# Schematic.net
KiCad netlist of a schematic drawn in EAGLE
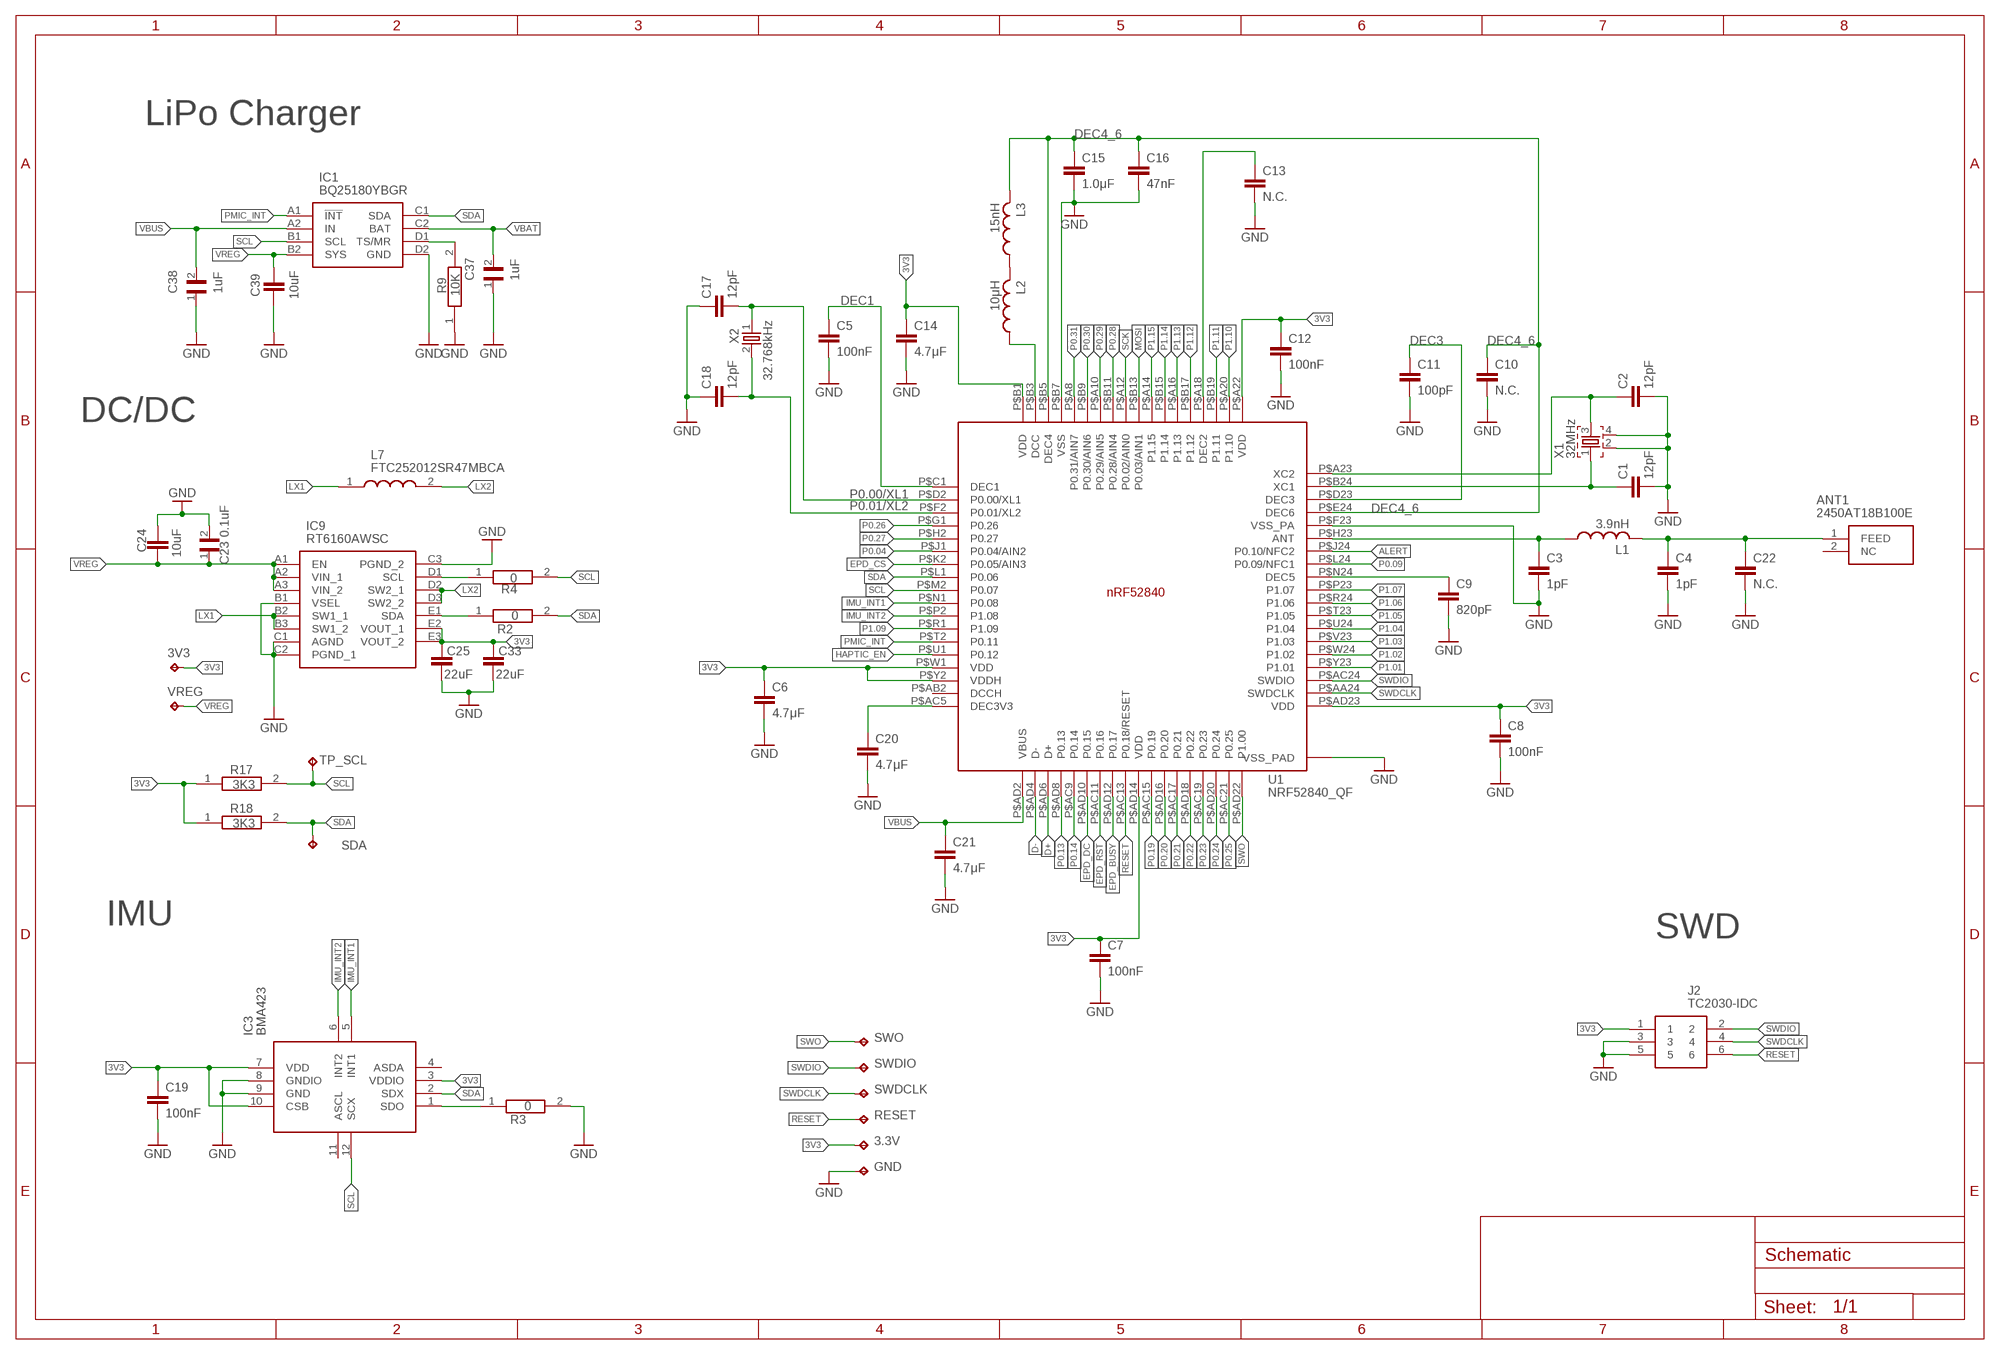
[diagram p0: schematic, sheet 1, part 1 of 2]
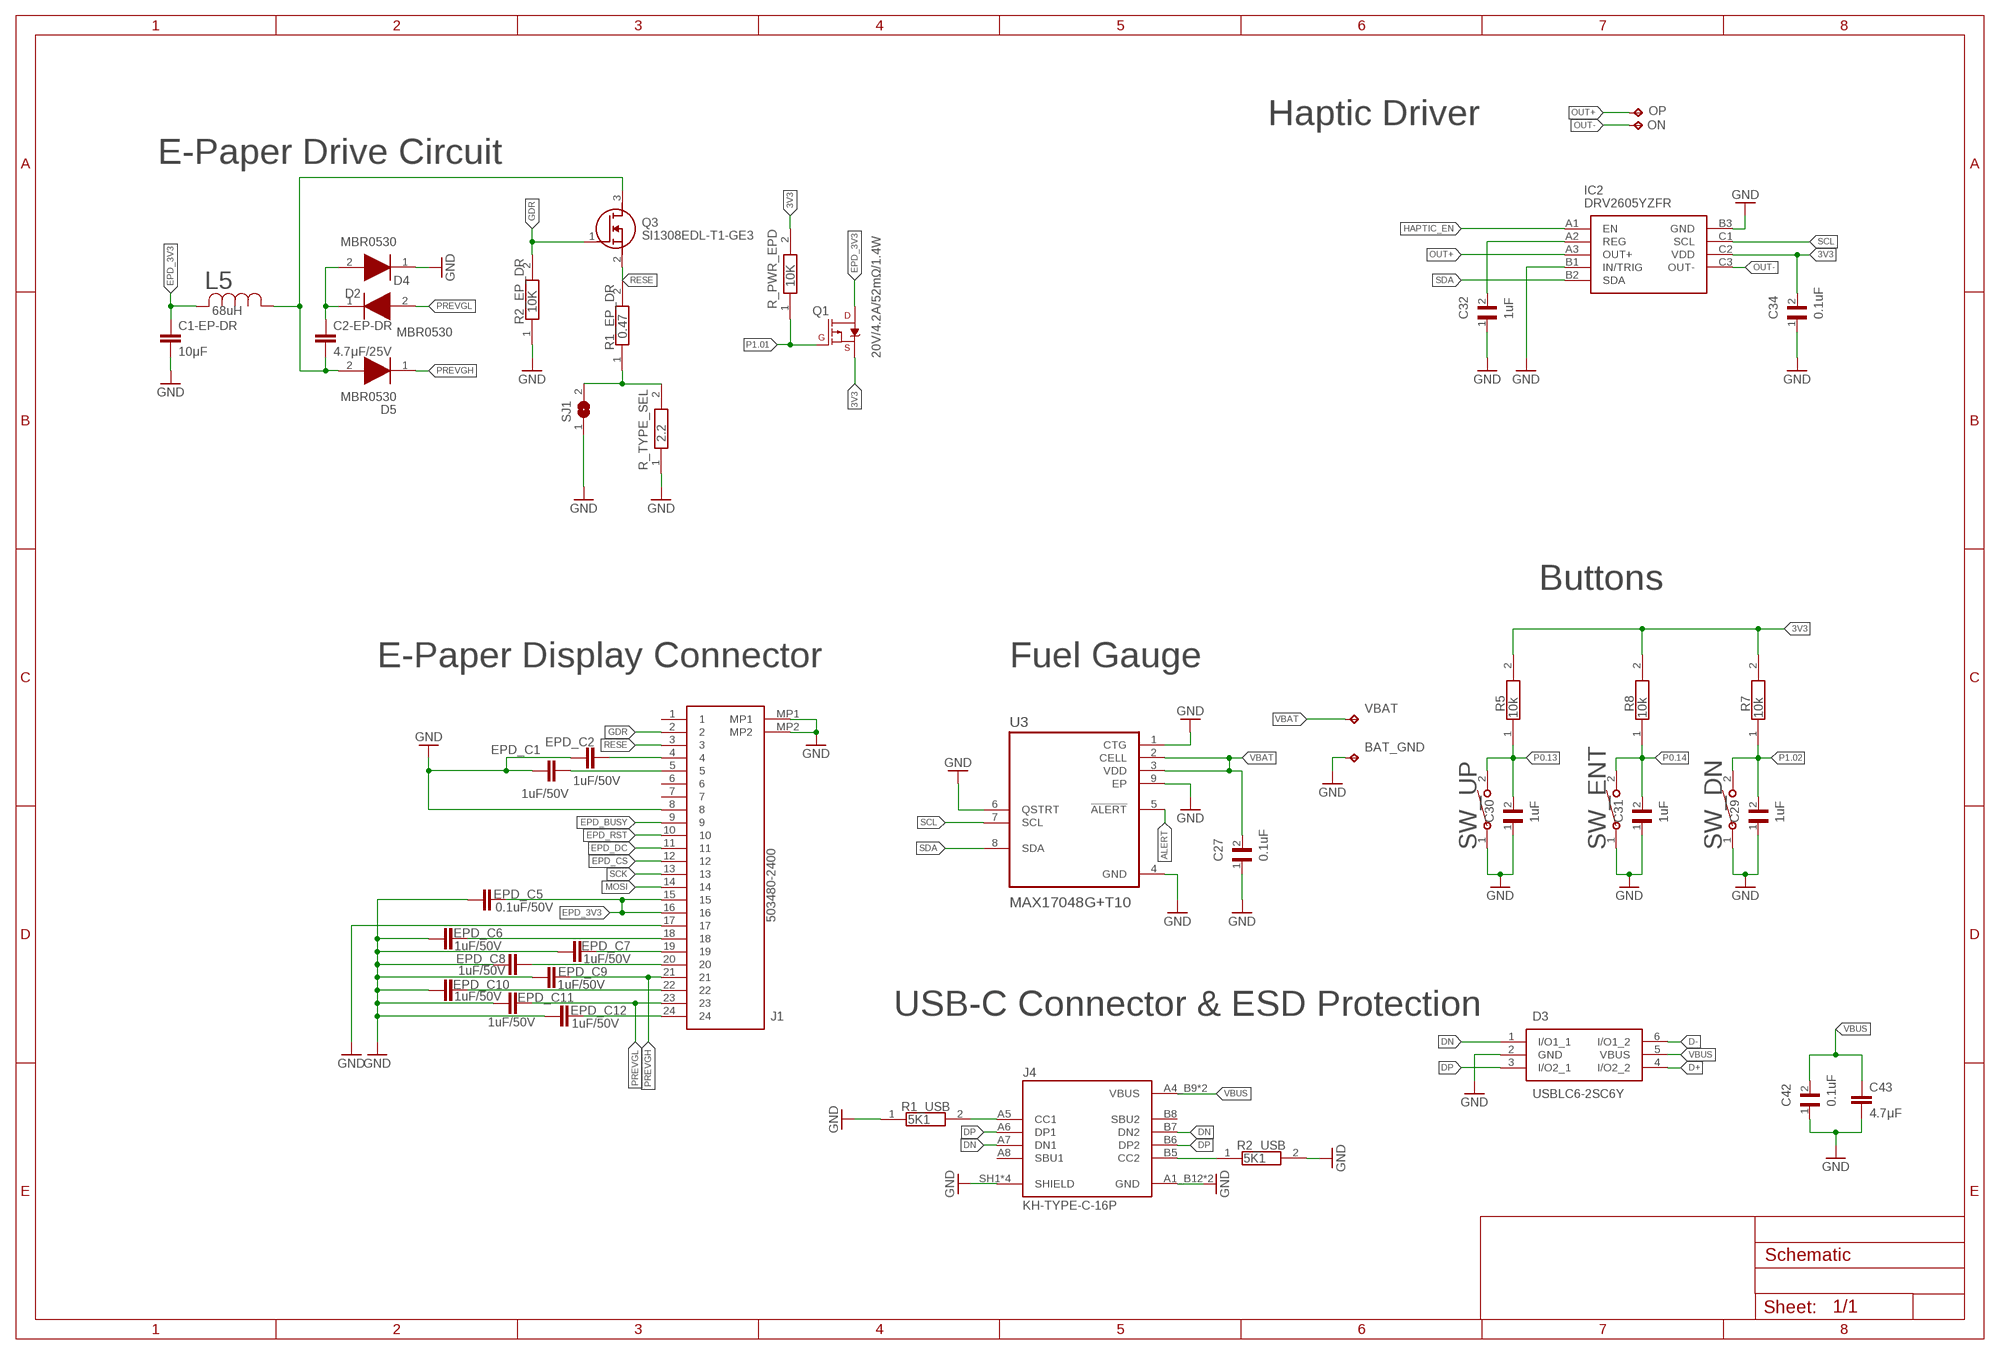
[diagram p1: schematic, sheet 1, part 2 of 2]

(export (version "E")
  (design (tool "Eeschema 10.0.6"))
  (components
    (comp (ref "3.3V")
      (value "HECTOR_WATCH_1_TPTP20R")
      (footprint "eagle-import:HECTOR_WATCH_1_TP20R")
      (libsource (lib "eagle-import") (part "HECTOR_WATCH_1_TPTP20R"))
    )
    (comp (ref "3V3")
      (value "HECTOR_WATCH_1_TPTP20R")
      (footprint "eagle-import:HECTOR_WATCH_1_TP20R")
      (libsource (lib "eagle-import") (part "HECTOR_WATCH_1_TPTP20R"))
    )
    (comp (ref "ANT1")
      (value "2450AT18B100E")
      (footprint "eagle-import:2450AT18B100E_ANTC3216X140N")
      (fields (field (name "MOUSER_PART_NUMBER") "609-2450AT18B100E"))
      (libsource (lib "eagle-import") (part "2450AT18B100E_2450AT18B100E"))
    )
    (comp (ref "BAT_GND")
      (value "HECTOR_WATCH_1_TPTP20R")
      (footprint "eagle-import:HECTOR_WATCH_1_TP20R")
      (libsource (lib "eagle-import") (part "HECTOR_WATCH_1_TPTP20R"))
    )
    (comp (ref "C1")
      (value "12pF")
      (footprint "eagle-import:GRM011R60J152KE01L_2_CAPC0201X13N")
      (libsource (lib "eagle-import") (part "NORDIC_NRF_3_CAPACITOR_0201_L"))
    )
    (comp (ref "C1-EP-DR")
      (value "10μF")
      (footprint "eagle-import:NORDIC_NRF_2_RESC0402_L")
      (libsource (lib "eagle-import") (part "NORDIC_NRF_3_CAPACITOR_0402_L"))
    )
    (comp (ref "C2")
      (value "12pF")
      (footprint "eagle-import:GRM011R60J152KE01L_2_CAPC0201X13N")
      (libsource (lib "eagle-import") (part "NORDIC_NRF_3_CAPACITOR_0201_L"))
    )
    (comp (ref "C2-EP-DR")
      (value "4.7μF/25V")
      (footprint "eagle-import:NORDIC_NRF_2_RESC0402_L")
      (libsource (lib "eagle-import") (part "NORDIC_NRF_3_CAPACITOR_0402_L"))
    )
    (comp (ref "C3")
      (value "1pF")
      (footprint "eagle-import:GRM011R60J152KE01L_2_CAPC0201X13N")
      (libsource (lib "eagle-import") (part "NORDIC_NRF_3_CAPACITOR_0201_L"))
    )
    (comp (ref "C4")
      (value "1pF")
      (footprint "eagle-import:GRM011R60J152KE01L_2_CAPC0201X13N")
      (libsource (lib "eagle-import") (part "NORDIC_NRF_3_CAPACITOR_0201_L"))
    )
    (comp (ref "C5")
      (value "100nF")
      (footprint "eagle-import:GRM011R60J152KE01L_2_CAPC0201X13N")
      (libsource (lib "eagle-import") (part "NORDIC_NRF_3_CAPACITOR_0201_L"))
    )
    (comp (ref "C6")
      (value "4.7μF")
      (footprint "eagle-import:NORDIC_NRF_2_RESC0402_L")
      (libsource (lib "eagle-import") (part "NORDIC_NRF_3_CAPACITOR_0402_L"))
    )
    (comp (ref "C7")
      (value "100nF")
      (footprint "eagle-import:GRM011R60J152KE01L_2_CAPC0201X13N")
      (libsource (lib "eagle-import") (part "NORDIC_NRF_3_CAPACITOR_0201_L"))
    )
    (comp (ref "C8")
      (value "100nF")
      (footprint "eagle-import:GRM011R60J152KE01L_2_CAPC0201X13N")
      (libsource (lib "eagle-import") (part "NORDIC_NRF_3_CAPACITOR_0201_L"))
    )
    (comp (ref "C9")
      (value "820pF")
      (footprint "eagle-import:GRM011R60J152KE01L_2_CAPC0201X13N")
      (libsource (lib "eagle-import") (part "NORDIC_NRF_3_CAPACITOR_0201_L"))
    )
    (comp (ref "C10")
      (value "N.C.")
      (footprint "eagle-import:GRM011R60J152KE01L_2_CAPC0201X13N")
      (libsource (lib "eagle-import") (part "NORDIC_NRF_3_CAPACITOR_0201_L"))
    )
    (comp (ref "C11")
      (value "100pF")
      (footprint "eagle-import:GRM011R60J152KE01L_2_CAPC0201X13N")
      (libsource (lib "eagle-import") (part "NORDIC_NRF_3_CAPACITOR_0201_L"))
    )
    (comp (ref "C12")
      (value "100nF")
      (footprint "eagle-import:GRM011R60J152KE01L_2_CAPC0201X13N")
      (libsource (lib "eagle-import") (part "NORDIC_NRF_3_CAPACITOR_0201_L"))
    )
    (comp (ref "C13")
      (value "N.C.")
      (footprint "eagle-import:GRM011R60J152KE01L_2_CAPC0201X13N")
      (libsource (lib "eagle-import") (part "NORDIC_NRF_3_CAPACITOR_0201_L"))
    )
    (comp (ref "C14")
      (value "4.7μF")
      (footprint "eagle-import:NORDIC_NRF_2_RESC0402_L")
      (libsource (lib "eagle-import") (part "NORDIC_NRF_3_CAPACITOR_0402_L"))
    )
    (comp (ref "C15")
      (value "1.0μF")
      (footprint "eagle-import:NORDIC_NRF_2_RESC0402_L")
      (libsource (lib "eagle-import") (part "NORDIC_NRF_3_CAPACITOR_0402_L"))
    )
    (comp (ref "C16")
      (value "47nF")
      (footprint "eagle-import:GRM011R60J152KE01L_2_CAPC0201X13N")
      (libsource (lib "eagle-import") (part "NORDIC_NRF_3_CAPACITOR_0201_L"))
    )
    (comp (ref "C17")
      (value "12pF")
      (footprint "eagle-import:GRM011R60J152KE01L_2_CAPC0201X13N")
      (libsource (lib "eagle-import") (part "NORDIC_NRF_3_CAPACITOR_0201_L"))
    )
    (comp (ref "C18")
      (value "12pF")
      (footprint "eagle-import:GRM011R60J152KE01L_2_CAPC0201X13N")
      (libsource (lib "eagle-import") (part "NORDIC_NRF_3_CAPACITOR_0201_L"))
    )
    (comp (ref "C19")
      (value "100nF")
      (footprint "eagle-import:GRM011R60J152KE01L_2_CAPC0201X13N")
      (libsource (lib "eagle-import") (part "NORDIC_NRF_3_CAPACITOR_0201_L"))
    )
    (comp (ref "C20")
      (value "4.7μF")
      (footprint "eagle-import:NORDIC_NRF_2_RESC0402_L")
      (libsource (lib "eagle-import") (part "NORDIC_NRF_3_CAPACITOR_0402_L"))
    )
    (comp (ref "C21")
      (value "4.7μF")
      (footprint "eagle-import:NORDIC_NRF_2_RESC0402_L")
      (libsource (lib "eagle-import") (part "NORDIC_NRF_3_CAPACITOR_0402_L"))
    )
    (comp (ref "C22")
      (value "N.C.")
      (footprint "eagle-import:GRM011R60J152KE01L_2_CAPC0201X13N")
      (libsource (lib "eagle-import") (part "NORDIC_NRF_3_CAPACITOR_0201_L"))
    )
    (comp (ref "C23")
      (value "0.1uF")
      (footprint "eagle-import:GRM011R60J152KE01L_2_CAPC0201X13N")
      (fields (field (name "MF") "Murata") (field (name "MP") "GRM011R60J152KE01L"))
      (libsource (lib "eagle-import") (part "GRM011R60J152KE01L_2_GRM011R60J152KE01L"))
    )
    (comp (ref "C24")
      (value "10uF")
      (footprint "eagle-import:PERFECT_0402_0402")
      (libsource (lib "eagle-import") (part "PERFECT_0402_CAP_0402"))
    )
    (comp (ref "C25")
      (value "22uF")
      (footprint "eagle-import:PERFECT_0402_0402")
      (libsource (lib "eagle-import") (part "PERFECT_0402_CAP_0402"))
    )
    (comp (ref "C27")
      (value "0.1uF")
      (footprint "eagle-import:GRM011R60J152KE01L_2_CAPC0201X13N")
      (fields (field (name "MF") "Murata") (field (name "MP") "GRM011R60J152KE01L"))
      (libsource (lib "eagle-import") (part "GRM011R60J152KE01L_2_GRM011R60J152KE01L"))
    )
    (comp (ref "C29")
      (value "1uF")
      (footprint "eagle-import:GRM011R60J152KE01L_2_CAPC0201X13N")
      (fields (field (name "MF") "Murata") (field (name "MP") "GRM011R60J152KE01L"))
      (libsource (lib "eagle-import") (part "GRM011R60J152KE01L_2_GRM011R60J152KE01L"))
    )
    (comp (ref "C30")
      (value "1uF")
      (footprint "eagle-import:GRM011R60J152KE01L_2_CAPC0201X13N")
      (fields (field (name "MF") "Murata") (field (name "MP") "GRM011R60J152KE01L"))
      (libsource (lib "eagle-import") (part "GRM011R60J152KE01L_2_GRM011R60J152KE01L"))
    )
    (comp (ref "C31")
      (value "1uF")
      (footprint "eagle-import:GRM011R60J152KE01L_2_CAPC0201X13N")
      (fields (field (name "MF") "Murata") (field (name "MP") "GRM011R60J152KE01L"))
      (libsource (lib "eagle-import") (part "GRM011R60J152KE01L_2_GRM011R60J152KE01L"))
    )
    (comp (ref "C32")
      (value "1uF")
      (footprint "eagle-import:GRM011R60J152KE01L_2_CAPC0201X13N")
      (fields (field (name "MF") "Murata") (field (name "MP") "GRM011R60J152KE01L"))
      (libsource (lib "eagle-import") (part "GRM011R60J152KE01L_2_GRM011R60J152KE01L"))
    )
    (comp (ref "C33")
      (value "22uF")
      (footprint "eagle-import:PERFECT_0402_0402")
      (libsource (lib "eagle-import") (part "PERFECT_0402_CAP_0402"))
    )
    (comp (ref "C34")
      (value "0.1uF")
      (footprint "eagle-import:GRM011R60J152KE01L_2_CAPC0201X13N")
      (fields (field (name "MF") "Murata") (field (name "MP") "GRM011R60J152KE01L"))
      (libsource (lib "eagle-import") (part "GRM011R60J152KE01L_2_GRM011R60J152KE01L"))
    )
    (comp (ref "C37")
      (value "1uF")
      (footprint "eagle-import:GRM011R60J152KE01L_2_CAPC0201X13N")
      (fields (field (name "MF") "Murata") (field (name "MP") "GRM011R60J152KE01L"))
      (libsource (lib "eagle-import") (part "GRM011R60J152KE01L_2_GRM011R60J152KE01L"))
    )
    (comp (ref "C38")
      (value "1uF")
      (footprint "eagle-import:GRM011R60J152KE01L_2_CAPC0201X13N")
      (fields (field (name "MF") "Murata") (field (name "MP") "GRM011R60J152KE01L"))
      (libsource (lib "eagle-import") (part "GRM011R60J152KE01L_2_GRM011R60J152KE01L"))
    )
    (comp (ref "C39")
      (value "10uF")
      (footprint "eagle-import:NORDIC_NRF_2_RESC0402_L")
      (libsource (lib "eagle-import") (part "NORDIC_NRF_3_CAPACITOR_0402_L"))
    )
    (comp (ref "C42")
      (value "0.1uF")
      (footprint "eagle-import:GRM011R60J152KE01L_2_CAPC0201X13N")
      (fields (field (name "MF") "Murata") (field (name "MP") "GRM011R60J152KE01L"))
      (libsource (lib "eagle-import") (part "GRM011R60J152KE01L_2_GRM011R60J152KE01L"))
    )
    (comp (ref "C43")
      (value "4.7μF")
      (footprint "eagle-import:NORDIC_NRF_2_RESC0402_L")
      (libsource (lib "eagle-import") (part "NORDIC_NRF_3_CAPACITOR_0402_L"))
    )
    (comp (ref "D2")
      (value "MBR0530")
      (footprint "eagle-import:ESP32_C6_LIBRARY_5_SOD3716X135N")
      (fields (field (name "MF") "ON Semiconductor"))
      (libsource (lib "eagle-import") (part "ESP32_C6_LIBRARY_5_MBR0530"))
    )
    (comp (ref "D3")
      (value "USBLC6-2SC6Y")
      (footprint "eagle-import:ESP32_C6_LIBRARY_3_SOT95P280X145-6N")
      (fields (field (name "MF") "STMicroelectronics"))
      (libsource (lib "eagle-import") (part "ESP32_C6_LIBRARY_3_USBLC6-2SC6Y"))
    )
    (comp (ref "D4")
      (value "MBR0530")
      (footprint "eagle-import:ESP32_C6_LIBRARY_5_SOD3716X135N")
      (fields (field (name "MF") "ON Semiconductor"))
      (libsource (lib "eagle-import") (part "ESP32_C6_LIBRARY_5_MBR0530"))
    )
    (comp (ref "D5")
      (value "MBR0530")
      (footprint "eagle-import:ESP32_C6_LIBRARY_5_SOD3716X135N")
      (fields (field (name "MF") "ON Semiconductor"))
      (libsource (lib "eagle-import") (part "ESP32_C6_LIBRARY_5_MBR0530"))
    )
    (comp (ref "EPD_C1")
      (value "1uF/50V")
      (footprint "eagle-import:GRM011R60J152KE01L_2_CAPC0201X13N")
      (libsource (lib "eagle-import") (part "NORDIC_NRF_3_CAPACITOR_0201_L"))
    )
    (comp (ref "EPD_C2")
      (value "1uF/50V")
      (footprint "eagle-import:GRM011R60J152KE01L_2_CAPC0201X13N")
      (libsource (lib "eagle-import") (part "NORDIC_NRF_3_CAPACITOR_0201_L"))
    )
    (comp (ref "EPD_C5")
      (value "0.1uF/50V")
      (footprint "eagle-import:GRM011R60J152KE01L_2_CAPC0201X13N")
      (libsource (lib "eagle-import") (part "NORDIC_NRF_3_CAPACITOR_0201_L"))
    )
    (comp (ref "EPD_C6")
      (value "1uF/50V")
      (footprint "eagle-import:GRM011R60J152KE01L_2_CAPC0201X13N")
      (libsource (lib "eagle-import") (part "NORDIC_NRF_3_CAPACITOR_0201_L"))
    )
    (comp (ref "EPD_C7")
      (value "1uF/50V")
      (footprint "eagle-import:GRM011R60J152KE01L_2_CAPC0201X13N")
      (libsource (lib "eagle-import") (part "NORDIC_NRF_3_CAPACITOR_0201_L"))
    )
    (comp (ref "EPD_C8")
      (value "1uF/50V")
      (footprint "eagle-import:GRM011R60J152KE01L_2_CAPC0201X13N")
      (libsource (lib "eagle-import") (part "NORDIC_NRF_3_CAPACITOR_0201_L"))
    )
    (comp (ref "EPD_C9")
      (value "1uF/50V")
      (footprint "eagle-import:GRM011R60J152KE01L_2_CAPC0201X13N")
      (libsource (lib "eagle-import") (part "NORDIC_NRF_3_CAPACITOR_0201_L"))
    )
    (comp (ref "EPD_C10")
      (value "1uF/50V")
      (footprint "eagle-import:GRM011R60J152KE01L_2_CAPC0201X13N")
      (libsource (lib "eagle-import") (part "NORDIC_NRF_3_CAPACITOR_0201_L"))
    )
    (comp (ref "EPD_C11")
      (value "1uF/50V")
      (footprint "eagle-import:GRM011R60J152KE01L_2_CAPC0201X13N")
      (libsource (lib "eagle-import") (part "NORDIC_NRF_3_CAPACITOR_0201_L"))
    )
    (comp (ref "EPD_C12")
      (value "1uF/50V")
      (footprint "eagle-import:GRM011R60J152KE01L_2_CAPC0201X13N")
      (libsource (lib "eagle-import") (part "NORDIC_NRF_3_CAPACITOR_0201_L"))
    )
    (comp (ref "GND")
      (value "HECTOR_WATCH_1_TPTP20R")
      (footprint "eagle-import:HECTOR_WATCH_1_TP20R")
      (libsource (lib "eagle-import") (part "HECTOR_WATCH_1_TPTP20R"))
    )
    (comp (ref "IC1")
      (value "BQ25180YBGR")
      (footprint "eagle-import:BQ25180YBGR_BGA8C40P2X4_100X155X50")
      (fields (field (name "MOUSER_PART_NUMBER") "595-BQ25180YBGR"))
      (libsource (lib "eagle-import") (part "BQ25180YBGR_BQ25180YBGR"))
    )
    (comp (ref "IC2")
      (value "DRV2605YZFR")
      (footprint "eagle-import:DRV2605YZFR_BGA9C50P3X3_144X144X62")
      (libsource (lib "eagle-import") (part "DRV2605YZFR_DRV2605YZFR"))
    )
    (comp (ref "IC3")
      (value "BMA423")
      (footprint "eagle-import:BMA423_BMA423")
      (fields (field (name "MOUSER_PART_NUMBER") "262-BMA423"))
      (libsource (lib "eagle-import") (part "BMA423_BMA423"))
    )
    (comp (ref "IC9")
      (value "RT6160AWSC")
      (footprint "eagle-import:RT6160AWSC_BGA15C40P3X5_140X230X60")
      (fields (field (name "MOUSER_PART_NUMBER") "835-RT6160AWSC"))
      (libsource (lib "eagle-import") (part "RT6160AWSC_RT6160AWSC"))
    )
    (comp (ref "J1")
      (value "503480-2400")
      (footprint "eagle-import:503480-2400_5034802400")
      (fields (field (name "MOUSER_PART_NUMBER") "538-503480-2400"))
      (libsource (lib "eagle-import") (part "503480-2400_503480-2400"))
    )
    (comp (ref "J2")
      (value "TC2030-IDC")
      (footprint "eagle-import:TC2030-IDC_TC2030IDC")
      (libsource (lib "eagle-import") (part "TC2030-IDC_TC2030-IDC"))
    )
    (comp (ref "J4")
      (value "KH-TYPE-C-16P")
      (footprint "eagle-import:KH-TYPE-C-16P_KINGHELM_KH-TYPE-C-16P")
      (fields (field (name "MF") "kinghelm"))
      (libsource (lib "eagle-import") (part "KH-TYPE-C-16P_KH-TYPE-C-16P"))
    )
    (comp (ref "L1")
      (value "3.9nH")
      (footprint "eagle-import:NORDIC_NRF_2_RESC0201_L")
      (libsource (lib "eagle-import") (part "NORDIC_NRF_2_INDUCTOR_0201_L"))
    )
    (comp (ref "L2")
      (value "10μH")
      (footprint "eagle-import:NORDIC_NRF_2_RESC0201_L")
      (libsource (lib "eagle-import") (part "NORDIC_NRF_2_INDUCTOR_0201_L"))
    )
    (comp (ref "L3")
      (value "15nH")
      (footprint "eagle-import:NORDIC_NRF_2_RESC0201_L")
      (libsource (lib "eagle-import") (part "NORDIC_NRF_2_INDUCTOR_0201_L"))
    )
    (comp (ref "L5")
      (value "68uH")
      (footprint "eagle-import:ESP32_C6_LIBRARY_2_IND_4828-WE-TPC_WRE")
      (fields
        (field (name "MANUFACTURER_PART_NUMBER") "744043680")
        (field (name "COPYRIGHT") "Copyright (C) 2024 Ultra Librarian. All rights reserved.")
      )
      (libsource (lib "eagle-import") (part "ESP32_C6_LIBRARY_2_744043680IND_4828-WE-TPC_WRE"))
    )
    (comp (ref "L7")
      (value "FTC252012SR47MBCA")
      (footprint "eagle-import:MLP2016SR47MT0S1_INDC2016X100N")
      (libsource (lib "eagle-import") (part "MLP2016SR47MT0S1_FTC252012SR47MBCA"))
    )
    (comp (ref "ON")
      (value "HECTOR_WATCH_1_TPTP20R")
      (footprint "eagle-import:HECTOR_WATCH_1_TP20R")
      (libsource (lib "eagle-import") (part "HECTOR_WATCH_1_TPTP20R"))
    )
    (comp (ref "OP")
      (value "HECTOR_WATCH_1_TPTP20R")
      (footprint "eagle-import:HECTOR_WATCH_1_TP20R")
      (libsource (lib "eagle-import") (part "HECTOR_WATCH_1_TPTP20R"))
    )
    (comp (ref "Q1")
      (value "20V/4.2A/52mΩ/1.4W")
      (footprint "eagle-import:ESP32_C6_LIBRARY_4_ESP32_C6_LIBRARY_4_ESP32_C6_LIBRARY_4_ESP32_C6_LIBRARY_4_ESP32_WROVER_SPARKFUN-DISCRETESEMI_SOT23-3")
      (libsource (lib "eagle-import") (part "ESP32_C6_LIBRARY_4_ESP32_WROVER_SPARKFUN-DISCRETESEMI_MOSFET_PCH-DMG2305UX-7"))
    )
    (comp (ref "Q3")
      (value "SI1308EDL-T1-GE3")
      (footprint "eagle-import:ESP32_C6_LIBRARY_6_SOT65P210X110-3N")
      (fields (field (name "MF") "Vishay Siliconix"))
      (libsource (lib "eagle-import") (part "ESP32_C6_LIBRARY_6_SI1308EDL-T1-GE3"))
    )
    (comp (ref "R1_EP_DR")
      (value "0.47")
      (footprint "eagle-import:ERA-1AEB3401C_0201")
      (libsource (lib "eagle-import") (part "CPF0201D7K68C1_CPF0201D7K68C1"))
    )
    (comp (ref "R1_USB")
      (value "5K1")
      (footprint "eagle-import:ERA-1AEB3401C_0201")
      (libsource (lib "eagle-import") (part "CPF0201D7K68C1_CPF0201D7K68C1"))
    )
    (comp (ref "R2")
      (value "0")
      (footprint "eagle-import:ERA-1AEB3401C_0201")
      (fields (field (name "RESISTANCE") "0"))
      (libsource (lib "eagle-import") (part "CPF0201D7K68C1_CPF0201D7K68C1"))
    )
    (comp (ref "R2_EP_DR")
      (value "10K")
      (footprint "eagle-import:ERA-1AEB3401C_0201")
      (libsource (lib "eagle-import") (part "CPF0201D7K68C1_CPF0201D7K68C1"))
    )
    (comp (ref "R2_USB")
      (value "5K1")
      (footprint "eagle-import:ERA-1AEB3401C_0201")
      (libsource (lib "eagle-import") (part "CPF0201D7K68C1_CPF0201D7K68C1"))
    )
    (comp (ref "R3")
      (value "0")
      (footprint "eagle-import:ERA-1AEB3401C_0201")
      (fields (field (name "RESISTANCE") "0"))
      (libsource (lib "eagle-import") (part "CPF0201D7K68C1_CPF0201D7K68C1"))
    )
    (comp (ref "R4")
      (value "0")
      (footprint "eagle-import:ERA-1AEB3401C_0201")
      (fields (field (name "RESISTANCE") "0"))
      (libsource (lib "eagle-import") (part "CPF0201D7K68C1_CPF0201D7K68C1"))
    )
    (comp (ref "R5")
      (value "10k")
      (footprint "eagle-import:ERA-1AEB3401C_0201")
      (libsource (lib "eagle-import") (part "CPF0201D7K68C1_CPF0201D7K68C1"))
    )
    (comp (ref "R7")
      (value "10k")
      (footprint "eagle-import:ERA-1AEB3401C_0201")
      (libsource (lib "eagle-import") (part "CPF0201D7K68C1_CPF0201D7K68C1"))
    )
    (comp (ref "R8")
      (value "10k")
      (footprint "eagle-import:ERA-1AEB3401C_0201")
      (libsource (lib "eagle-import") (part "CPF0201D7K68C1_CPF0201D7K68C1"))
    )
    (comp (ref "R9")
      (value "10K")
      (footprint "eagle-import:ERA-1AEB3401C_0201")
      (fields (field (name "RESISTANCE") "10K"))
      (libsource (lib "eagle-import") (part "CPF0201D7K68C1_CPF0201D7K68C1"))
    )
    (comp (ref "R17")
      (value "3K3")
      (footprint "eagle-import:ERA-1AEB3401C_0201")
      (fields (field (name "RESISTANCE") "3K3"))
      (libsource (lib "eagle-import") (part "CPF0201D7K68C1_CPF0201D7K68C1"))
    )
    (comp (ref "R18")
      (value "3K3")
      (footprint "eagle-import:ERA-1AEB3401C_0201")
      (fields (field (name "RESISTANCE") "3K3"))
      (libsource (lib "eagle-import") (part "CPF0201D7K68C1_CPF0201D7K68C1"))
    )
    (comp (ref "RESET")
      (value "HECTOR_WATCH_1_TPTP20R")
      (footprint "eagle-import:HECTOR_WATCH_1_TP20R")
      (libsource (lib "eagle-import") (part "HECTOR_WATCH_1_TPTP20R"))
    )
    (comp (ref "R_PWR_EPD")
      (value "10K")
      (footprint "eagle-import:ERA-1AEB3401C_0201")
      (libsource (lib "eagle-import") (part "CPF0201D7K68C1_CPF0201D7K68C1"))
    )
    (comp (ref "R_TYPE_SEL")
      (value "2.2")
      (footprint "eagle-import:ERA-1AEB3401C_0201")
      (libsource (lib "eagle-import") (part "CPF0201D7K68C1_CPF0201D7K68C1"))
    )
    (comp (ref "SDA")
      (value "HECTOR_WATCH_1_TPTP20R")
      (footprint "eagle-import:HECTOR_WATCH_1_TP20R")
      (libsource (lib "eagle-import") (part "HECTOR_WATCH_1_TPTP20R"))
    )
    (comp (ref "SJ1")
      (value "ESP32_C6_LIBRARY_7_JUMPER_SJ")
      (footprint "eagle-import:ESP32_C6_LIBRARY_7_JUMPER_SJ")
      (libsource (lib "eagle-import") (part "ESP32_C6_LIBRARY_7_JUMPER_SJ"))
    )
    (comp (ref "SWDCLK")
      (value "HECTOR_WATCH_1_TPTP20R")
      (footprint "eagle-import:HECTOR_WATCH_1_TP20R")
      (libsource (lib "eagle-import") (part "HECTOR_WATCH_1_TPTP20R"))
    )
    (comp (ref "SWDIO")
      (value "HECTOR_WATCH_1_TPTP20R")
      (footprint "eagle-import:HECTOR_WATCH_1_TP20R")
      (libsource (lib "eagle-import") (part "HECTOR_WATCH_1_TPTP20R"))
    )
    (comp (ref "SWO")
      (value "HECTOR_WATCH_1_TPTP20R")
      (footprint "eagle-import:HECTOR_WATCH_1_TP20R")
      (libsource (lib "eagle-import") (part "HECTOR_WATCH_1_TPTP20R"))
    )
    (comp (ref "SW_DN")
      (value "2025-10-22_07-23-44_LIBRARY_EVP-AKE31ASW_EVP-AKE31A_PAN")
      (footprint "eagle-import:2025-10-22_07-23-44_LIBRARY_SW_EVP-AKE31A_PAN")
      (fields
        (field (name "MANUFACTURER_PART_NUMBER") "EVP-AKE31A")
        (field (name "COPYRIGHT") "Copyright (C) 2025 Ultra Librarian. All rights reserved.")
      )
      (libsource (lib "eagle-import") (part "2025-10-22_07-23-44_LIBRARY_EVP-AKE31ASW_EVP-AKE31A_PAN"))
    )
    (comp (ref "SW_ENT")
      (value "2025-10-22_07-23-44_LIBRARY_EVP-AKE31ASW_EVP-AKE31A_PAN")
      (footprint "eagle-import:2025-10-22_07-23-44_LIBRARY_SW_EVP-AKE31A_PAN")
      (fields
        (field (name "MANUFACTURER_PART_NUMBER") "EVP-AKE31A")
        (field (name "COPYRIGHT") "Copyright (C) 2025 Ultra Librarian. All rights reserved.")
      )
      (libsource (lib "eagle-import") (part "2025-10-22_07-23-44_LIBRARY_EVP-AKE31ASW_EVP-AKE31A_PAN"))
    )
    (comp (ref "SW_UP")
      (value "2025-10-22_07-23-44_LIBRARY_EVP-AKE31ASW_EVP-AKE31A_PAN")
      (footprint "eagle-import:2025-10-22_07-23-44_LIBRARY_SW_EVP-AKE31A_PAN")
      (fields
        (field (name "MANUFACTURER_PART_NUMBER") "EVP-AKE31A")
        (field (name "COPYRIGHT") "Copyright (C) 2025 Ultra Librarian. All rights reserved.")
      )
      (libsource (lib "eagle-import") (part "2025-10-22_07-23-44_LIBRARY_EVP-AKE31ASW_EVP-AKE31A_PAN"))
    )
    (comp (ref "TP_SCL")
      (value "HECTOR_WATCH_1_TPTP20R")
      (footprint "eagle-import:HECTOR_WATCH_1_TP20R")
      (libsource (lib "eagle-import") (part "HECTOR_WATCH_1_TPTP20R"))
    )
    (comp (ref "U1")
      (value "NRF52840_QF")
      (footprint "eagle-import:NORDIC_NRF_4_AQFN50P700X700X85_HS-74N")
      (libsource (lib "eagle-import") (part "NORDIC_NRF_4_NRF52840_QF"))
    )
    (comp (ref "U3")
      (value "MAX17048G+T10")
      (footprint "eagle-import:ESP32_C6_LIBRARY_SON50P200X200X80-9N")
      (fields (field (name "MF") "Analog Devices"))
      (libsource (lib "eagle-import") (part "ESP32_C6_LIBRARY_MAX17048G+T10"))
    )
    (comp (ref "VBAT")
      (value "HECTOR_WATCH_1_TPTP20R")
      (footprint "eagle-import:HECTOR_WATCH_1_TP20R")
      (libsource (lib "eagle-import") (part "HECTOR_WATCH_1_TPTP20R"))
    )
    (comp (ref "VREG")
      (value "HECTOR_WATCH_1_TPTP20R")
      (footprint "eagle-import:HECTOR_WATCH_1_TP20R")
      (libsource (lib "eagle-import") (part "HECTOR_WATCH_1_TPTP20R"))
    )
    (comp (ref "X1")
      (value "32MHz")
      (footprint "eagle-import:NORDIC_NRF_BT-XTAL_2016_N")
      (libsource (lib "eagle-import") (part "NORDIC_NRF_XTAL_32MHZ"))
    )
    (comp (ref "X2")
      (value "32.768kHz")
      (footprint "eagle-import:NORDIC_NRF_BT-XTAL_2016_N")
      (libsource (lib "eagle-import") (part "NORDIC_NRF_1_XTAL_32KHZ"))
    )
  )
  (nets
    (net (code "1") (name "/DEC1") (class "Default")
      (node (ref "C5") (pin "1") (pinfunction "1_1") (pintype "passive"))
      (node (ref "U1") (pin "P$C1") (pinfunction "DEC1_P$C1") (pintype "power_in"))
    )
    (net (code "2") (name "/DEC3") (class "Default")
      (node (ref "C11") (pin "1") (pinfunction "1_1") (pintype "passive"))
      (node (ref "U1") (pin "P$D23") (pinfunction "DEC3_P$D23") (pintype "bidirectional"))
    )
    (net (code "3") (name "/DEC4_6") (class "Default")
      (node (ref "C10") (pin "1") (pinfunction "1_1") (pintype "passive"))
      (node (ref "C15") (pin "1") (pinfunction "1_1") (pintype "passive"))
      (node (ref "C16") (pin "1") (pinfunction "1_1") (pintype "passive"))
      (node (ref "L3") (pin "2") (pinfunction "2_2") (pintype "passive"))
      (node (ref "U1") (pin "P$B5") (pinfunction "DEC4_P$B5") (pintype "power_in"))
      (node (ref "U1") (pin "P$E24") (pinfunction "DEC6_P$E24") (pintype "bidirectional"))
    )
    (net (code "4") (name "/P0.00{slash}XL1") (class "Default")
      (node (ref "C17") (pin "2") (pinfunction "2_2") (pintype "passive"))
      (node (ref "U1") (pin "P$D2") (pinfunction "P0.00/XL1_P$D2") (pintype "bidirectional"))
      (node (ref "X2") (pin "1") (pinfunction "1_1") (pintype "passive"))
    )
    (net (code "5") (name "/P0.01{slash}XL2") (class "Default")
      (node (ref "C18") (pin "2") (pinfunction "2_2") (pintype "passive"))
      (node (ref "U1") (pin "P$F2") (pinfunction "P0.01/XL2_P$F2") (pintype "bidirectional"))
      (node (ref "X2") (pin "2") (pinfunction "2_2") (pintype "passive"))
    )
    (net (code "6") (name "3V3") (class "Default")
      (node (ref "3.3V") (pin "TP") (pinfunction "TP_TP") (pintype "input"))
      (node (ref "3V3") (pin "TP") (pinfunction "TP_TP") (pintype "input"))
      (node (ref "C12") (pin "1") (pinfunction "1_1") (pintype "passive"))
      (node (ref "C14") (pin "1") (pinfunction "1_1") (pintype "passive"))
      (node (ref "C19") (pin "1") (pinfunction "1_1") (pintype "passive"))
      (node (ref "C25") (pin "2") (pinfunction "2_2") (pintype "passive"))
      (node (ref "C33") (pin "2") (pinfunction "2_2") (pintype "passive"))
      (node (ref "C34") (pin "2") (pinfunction "2_2") (pintype "passive"))
      (node (ref "C6") (pin "1") (pinfunction "1_1") (pintype "passive"))
      (node (ref "C7") (pin "1") (pinfunction "1_1") (pintype "passive"))
      (node (ref "C8") (pin "1") (pinfunction "1_1") (pintype "passive"))
      (node (ref "IC2") (pin "C2") (pinfunction "VDD_C2") (pintype "bidirectional"))
      (node (ref "IC3") (pin "10") (pinfunction "CSB_10") (pintype "bidirectional"))
      (node (ref "IC3") (pin "3") (pinfunction "VDDIO_3") (pintype "bidirectional"))
      (node (ref "IC3") (pin "7") (pinfunction "VDD_7") (pintype "bidirectional"))
      (node (ref "IC9") (pin "E2") (pinfunction "VOUT_1_E2") (pintype "bidirectional"))
      (node (ref "IC9") (pin "E3") (pinfunction "VOUT_2_E3") (pintype "bidirectional"))
      (node (ref "J2") (pin "1") (pinfunction "1_1") (pintype "bidirectional"))
      (node (ref "Q1") (pin "2") (pinfunction "S_2") (pintype "bidirectional"))
      (node (ref "R17") (pin "1") (pinfunction "1_1") (pintype "bidirectional"))
      (node (ref "R18") (pin "1") (pinfunction "1_1") (pintype "bidirectional"))
      (node (ref "R5") (pin "2") (pinfunction "2_2") (pintype "bidirectional"))
      (node (ref "R7") (pin "2") (pinfunction "2_2") (pintype "bidirectional"))
      (node (ref "R8") (pin "2") (pinfunction "2_2") (pintype "bidirectional"))
      (node (ref "R_PWR_EPD") (pin "2") (pinfunction "2_2") (pintype "bidirectional"))
      (node (ref "U1") (pin "P$A22") (pinfunction "VDD_P$A22") (pintype "power_in"))
      (node (ref "U1") (pin "P$AD14") (pinfunction "VDD_P$AD14") (pintype "power_in"))
      (node (ref "U1") (pin "P$AD23") (pinfunction "VDD_P$AD23") (pintype "power_in"))
      (node (ref "U1") (pin "P$B1") (pinfunction "VDD_P$B1") (pintype "power_in"))
      (node (ref "U1") (pin "P$W1") (pinfunction "VDD_P$W1") (pintype "power_in"))
      (node (ref "U1") (pin "P$Y2") (pinfunction "VDDH_P$Y2") (pintype "power_in"))
    )
    (net (code "7") (name "ALERT") (class "Default")
      (node (ref "U1") (pin "P$J24") (pinfunction "P0.10/NFC2_P$J24") (pintype "bidirectional"))
      (node (ref "U3") (pin "5") (pinfunction "~{ALERT}_5") (pintype "output"))
    )
    (net (code "8") (name "D+") (class "Default")
      (node (ref "D3") (pin "4") (pinfunction "I/O2_2_4") (pintype "bidirectional"))
      (node (ref "U1") (pin "P$AD6") (pinfunction "D+_P$AD6") (pintype "bidirectional"))
    )
    (net (code "9") (name "D-") (class "Default")
      (node (ref "D3") (pin "6") (pinfunction "I/O1_2_6") (pintype "bidirectional"))
      (node (ref "U1") (pin "P$AD4") (pinfunction "D-_P$AD4") (pintype "bidirectional"))
    )
    (net (code "10") (name "DN") (class "Default")
      (node (ref "D3") (pin "1") (pinfunction "I/O1_1_1") (pintype "bidirectional"))
      (node (ref "J4") (pin "A7") (pinfunction "DN1_A7") (pintype "bidirectional"))
      (node (ref "J4") (pin "B7") (pinfunction "DN2_B7") (pintype "bidirectional"))
    )
    (net (code "11") (name "DP") (class "Default")
      (node (ref "D3") (pin "3") (pinfunction "I/O2_1_3") (pintype "bidirectional"))
      (node (ref "J4") (pin "A6") (pinfunction "DP1_A6") (pintype "bidirectional"))
      (node (ref "J4") (pin "B6") (pinfunction "DP2_B6") (pintype "bidirectional"))
    )
    (net (code "12") (name "EPD_3V3") (class "Default")
      (node (ref "C1-EP-DR") (pin "1") (pinfunction "1_1") (pintype "passive"))
      (node (ref "EPD_C5") (pin "2") (pinfunction "2_2") (pintype "passive"))
      (node (ref "J1") (pin "15") (pinfunction "15_15") (pintype "bidirectional"))
      (node (ref "J1") (pin "16") (pinfunction "16_16") (pintype "bidirectional"))
      (node (ref "L5") (pin "2") (pinfunction "2_2") (pintype "passive"))
      (node (ref "Q1") (pin "3") (pinfunction "D_3") (pintype "bidirectional"))
    )
    (net (code "13") (name "EPD_BUSY") (class "Default")
      (node (ref "J1") (pin "9") (pinfunction "9_9") (pintype "bidirectional"))
      (node (ref "U1") (pin "P$AD12") (pinfunction "P0.17_P$AD12") (pintype "bidirectional"))
    )
    (net (code "14") (name "EPD_CS") (class "Default")
      (node (ref "J1") (pin "12") (pinfunction "12_12") (pintype "bidirectional"))
      (node (ref "U1") (pin "P$K2") (pinfunction "P0.05/AIN3_P$K2") (pintype "bidirectional"))
    )
    (net (code "15") (name "EPD_DC") (class "Default")
      (node (ref "J1") (pin "11") (pinfunction "11_11") (pintype "bidirectional"))
      (node (ref "U1") (pin "P$AD10") (pinfunction "P0.15_P$AD10") (pintype "bidirectional"))
    )
    (net (code "16") (name "EPD_RST") (class "Default")
      (node (ref "J1") (pin "10") (pinfunction "10_10") (pintype "bidirectional"))
      (node (ref "U1") (pin "P$AC11") (pinfunction "P0.16_P$AC11") (pintype "bidirectional"))
    )
    (net (code "17") (name "GDR") (class "Default")
      (node (ref "J1") (pin "2") (pinfunction "2_2") (pintype "bidirectional"))
      (node (ref "Q3") (pin "1") (pinfunction "G_1") (pintype "bidirectional"))
      (node (ref "R2_EP_DR") (pin "2") (pinfunction "2_2") (pintype "bidirectional"))
    )
    (net (code "18") (name "GND") (class "Default")
      (node (ref "BAT_GND") (pin "TP") (pinfunction "TP_TP") (pintype "input"))
      (node (ref "C1") (pin "2") (pinfunction "2_2") (pintype "passive"))
      (node (ref "C1-EP-DR") (pin "2") (pinfunction "2_2") (pintype "passive"))
      (node (ref "C10") (pin "2") (pinfunction "2_2") (pintype "passive"))
      (node (ref "C11") (pin "2") (pinfunction "2_2") (pintype "passive"))
      (node (ref "C12") (pin "2") (pinfunction "2_2") (pintype "passive"))
      (node (ref "C13") (pin "2") (pinfunction "2_2") (pintype "passive"))
      (node (ref "C14") (pin "2") (pinfunction "2_2") (pintype "passive"))
      (node (ref "C15") (pin "2") (pinfunction "2_2") (pintype "passive"))
      (node (ref "C16") (pin "2") (pinfunction "2_2") (pintype "passive"))
      (node (ref "C17") (pin "1") (pinfunction "1_1") (pintype "passive"))
      (node (ref "C18") (pin "1") (pinfunction "1_1") (pintype "passive"))
      (node (ref "C19") (pin "2") (pinfunction "2_2") (pintype "passive"))
      (node (ref "C2") (pin "2") (pinfunction "2_2") (pintype "passive"))
      (node (ref "C20") (pin "2") (pinfunction "2_2") (pintype "passive"))
      (node (ref "C21") (pin "2") (pinfunction "2_2") (pintype "passive"))
      (node (ref "C22") (pin "2") (pinfunction "2_2") (pintype "passive"))
      (node (ref "C23") (pin "2") (pinfunction "2_2") (pintype "passive"))
      (node (ref "C24") (pin "1") (pinfunction "1_1") (pintype "passive"))
      (node (ref "C25") (pin "1") (pinfunction "1_1") (pintype "passive"))
      (node (ref "C27") (pin "1") (pinfunction "1_1") (pintype "passive"))
      (node (ref "C29") (pin "1") (pinfunction "1_1") (pintype "passive"))
      (node (ref "C3") (pin "2") (pinfunction "2_2") (pintype "passive"))
      (node (ref "C30") (pin "1") (pinfunction "1_1") (pintype "passive"))
      (node (ref "C31") (pin "1") (pinfunction "1_1") (pintype "passive"))
      (node (ref "C32") (pin "1") (pinfunction "1_1") (pintype "passive"))
      (node (ref "C33") (pin "1") (pinfunction "1_1") (pintype "passive"))
      (node (ref "C34") (pin "1") (pinfunction "1_1") (pintype "passive"))
      (node (ref "C37") (pin "1") (pinfunction "1_1") (pintype "passive"))
      (node (ref "C38") (pin "1") (pinfunction "1_1") (pintype "passive"))
      (node (ref "C39") (pin "2") (pinfunction "2_2") (pintype "passive"))
      (node (ref "C4") (pin "2") (pinfunction "2_2") (pintype "passive"))
      (node (ref "C42") (pin "1") (pinfunction "1_1") (pintype "passive"))
      (node (ref "C43") (pin "2") (pinfunction "2_2") (pintype "passive"))
      (node (ref "C5") (pin "2") (pinfunction "2_2") (pintype "passive"))
      (node (ref "C6") (pin "2") (pinfunction "2_2") (pintype "passive"))
      (node (ref "C7") (pin "2") (pinfunction "2_2") (pintype "passive"))
      (node (ref "C8") (pin "2") (pinfunction "2_2") (pintype "passive"))
      (node (ref "C9") (pin "2") (pinfunction "2_2") (pintype "passive"))
      (node (ref "D3") (pin "2") (pinfunction "GND_2") (pintype "bidirectional"))
      (node (ref "D4") (pin "1") (pinfunction "K_1") (pintype "bidirectional"))
      (node (ref "EPD_C1") (pin "1") (pinfunction "1_1") (pintype "passive"))
      (node (ref "EPD_C10") (pin "1") (pinfunction "1_1") (pintype "passive"))
      (node (ref "EPD_C11") (pin "1") (pinfunction "1_1") (pintype "passive"))
      (node (ref "EPD_C12") (pin "1") (pinfunction "1_1") (pintype "passive"))
      (node (ref "EPD_C2") (pin "1") (pinfunction "1_1") (pintype "passive"))
      (node (ref "EPD_C5") (pin "1") (pinfunction "1_1") (pintype "passive"))
      (node (ref "EPD_C6") (pin "1") (pinfunction "1_1") (pintype "passive"))
      (node (ref "EPD_C7") (pin "1") (pinfunction "1_1") (pintype "passive"))
      (node (ref "EPD_C8") (pin "1") (pinfunction "1_1") (pintype "passive"))
      (node (ref "EPD_C9") (pin "1") (pinfunction "1_1") (pintype "passive"))
      (node (ref "GND") (pin "TP") (pinfunction "TP_TP") (pintype "input"))
      (node (ref "IC1") (pin "D2") (pinfunction "GND_D2") (pintype "bidirectional"))
      (node (ref "IC2") (pin "B1") (pinfunction "IN/TRIG_B1") (pintype "bidirectional"))
      (node (ref "IC2") (pin "B3") (pinfunction "GND_B3") (pintype "bidirectional"))
      (node (ref "IC3") (pin "8") (pinfunction "GNDIO_8") (pintype "bidirectional"))
      (node (ref "IC3") (pin "9") (pinfunction "GND_9") (pintype "bidirectional"))
      (node (ref "IC9") (pin "B1") (pinfunction "VSEL_B1") (pintype "bidirectional"))
      (node (ref "IC9") (pin "C1") (pinfunction "AGND_C1") (pintype "bidirectional"))
      (node (ref "IC9") (pin "C2") (pinfunction "PGND_1_C2") (pintype "bidirectional"))
      (node (ref "IC9") (pin "C3") (pinfunction "PGND_2_C3") (pintype "bidirectional"))
      (node (ref "J1") (pin "17") (pinfunction "17_17") (pintype "bidirectional"))
      (node (ref "J1") (pin "8") (pinfunction "8_8") (pintype "bidirectional"))
      (node (ref "J1") (pin "MP1") (pinfunction "MP1_MP1") (pintype "bidirectional"))
      (node (ref "J1") (pin "MP2") (pinfunction "MP2_MP2") (pintype "bidirectional"))
      (node (ref "J2") (pin "3") (pinfunction "3_3") (pintype "bidirectional"))
      (node (ref "J2") (pin "5") (pinfunction "5_5") (pintype "bidirectional"))
      (node (ref "J4") (pin "A12_B1") (pinfunction "GND_A12_B1") (pintype "power_in"))
      (node (ref "J4") (pin "A1_B12") (pinfunction "GND_A1_B12") (pintype "power_in"))
      (node (ref "J4") (pin "SH1") (pinfunction "SHIELD_SH1") (pintype "passive"))
      (node (ref "J4") (pin "SH2") (pinfunction "SHIELD_SH2") (pintype "passive"))
      (node (ref "J4") (pin "SH3") (pinfunction "SHIELD_SH3") (pintype "passive"))
      (node (ref "J4") (pin "SH4") (pinfunction "SHIELD_SH4") (pintype "passive"))
      (node (ref "R1_USB") (pin "1") (pinfunction "1_1") (pintype "bidirectional"))
      (node (ref "R2_EP_DR") (pin "1") (pinfunction "1_1") (pintype "bidirectional"))
      (node (ref "R2_USB") (pin "2") (pinfunction "2_2") (pintype "bidirectional"))
      (node (ref "R3") (pin "2") (pinfunction "2_2") (pintype "bidirectional"))
      (node (ref "R9") (pin "1") (pinfunction "1_1") (pintype "bidirectional"))
      (node (ref "R_TYPE_SEL") (pin "1") (pinfunction "1_1") (pintype "bidirectional"))
      (node (ref "SJ1") (pin "1") (pinfunction "1_1") (pintype "passive"))
      (node (ref "SW_DN") (pin "1") (pinfunction "1_1") (pintype "passive"))
      (node (ref "SW_ENT") (pin "1") (pinfunction "1_1") (pintype "passive"))
      (node (ref "SW_UP") (pin "1") (pinfunction "1_1") (pintype "passive"))
      (node (ref "U1") (pin "P$74") (pinfunction "VSS_PAD_P$74") (pintype "bidirectional"))
      (node (ref "U1") (pin "P$75") (pinfunction "VSS_PAD_P$75") (pintype "bidirectional"))
      (node (ref "U1") (pin "P$76") (pinfunction "VSS_PAD_P$76") (pintype "bidirectional"))
      (node (ref "U1") (pin "P$77") (pinfunction "VSS_PAD_P$77") (pintype "bidirectional"))
      (node (ref "U1") (pin "P$78") (pinfunction "VSS_PAD_P$78") (pintype "bidirectional"))
      (node (ref "U1") (pin "P$79") (pinfunction "VSS_PAD_P$79") (pintype "bidirectional"))
      (node (ref "U1") (pin "P$80") (pinfunction "VSS_PAD_P$80") (pintype "bidirectional"))
      (node (ref "U1") (pin "P$81") (pinfunction "VSS_PAD_P$81") (pintype "bidirectional"))
      (node (ref "U1") (pin "P$82") (pinfunction "VSS_PAD_P$82") (pintype "bidirectional"))
      (node (ref "U1") (pin "P$83") (pinfunction "VSS_PAD_P$83") (pintype "bidirectional"))
      (node (ref "U1") (pin "P$84") (pinfunction "VSS_PAD_P$84") (pintype "bidirectional"))
      (node (ref "U1") (pin "P$85") (pinfunction "VSS_PAD_P$85") (pintype "bidirectional"))
      (node (ref "U1") (pin "P$86") (pinfunction "VSS_PAD_P$86") (pintype "bidirectional"))
      (node (ref "U1") (pin "P$87") (pinfunction "VSS_PAD_P$87") (pintype "bidirectional"))
      (node (ref "U1") (pin "P$88") (pinfunction "VSS_PAD_P$88") (pintype "bidirectional"))
      (node (ref "U1") (pin "P$89") (pinfunction "VSS_PAD_P$89") (pintype "bidirectional"))
      (node (ref "U1") (pin "P$90") (pinfunction "VSS_PAD_P$90") (pintype "bidirectional"))
      (node (ref "U1") (pin "P$B7") (pinfunction "VSS_P$B7") (pintype "power_in"))
      (node (ref "U1") (pin "P$F23") (pinfunction "VSS_PA_P$F23") (pintype "bidirectional"))
      (node (ref "U3") (pin "1") (pinfunction "CTG_1") (pintype "power_in"))
      (node (ref "U3") (pin "4") (pinfunction "GND_4") (pintype "power_in"))
      (node (ref "U3") (pin "6") (pinfunction "QSTRT_6") (pintype "input"))
      (node (ref "U3") (pin "9") (pinfunction "EP_9") (pintype "power_in"))
      (node (ref "X1") (pin "2") (pinfunction "2_2") (pintype "passive"))
      (node (ref "X1") (pin "4") (pinfunction "4_4") (pintype "passive"))
    )
    (net (code "19") (name "HAPTIC_EN") (class "Default")
      (node (ref "IC2") (pin "A1") (pinfunction "EN_A1") (pintype "bidirectional"))
      (node (ref "U1") (pin "P$U1") (pinfunction "P0.12_P$U1") (pintype "bidirectional"))
    )
    (net (code "20") (name "IMU_INT1") (class "Default")
      (node (ref "IC3") (pin "5") (pinfunction "INT1_5") (pintype "bidirectional"))
      (node (ref "U1") (pin "P$N1") (pinfunction "P0.08_P$N1") (pintype "bidirectional"))
    )
    (net (code "21") (name "IMU_INT2") (class "Default")
      (node (ref "IC3") (pin "6") (pinfunction "INT2_6") (pintype "bidirectional"))
      (node (ref "U1") (pin "P$P2") (pinfunction "P1.08_P$P2") (pintype "bidirectional"))
    )
    (net (code "22") (name "LX1") (class "Default")
      (node (ref "IC9") (pin "B2") (pinfunction "SW1_1_B2") (pintype "bidirectional"))
      (node (ref "IC9") (pin "B3") (pinfunction "SW1_2_B3") (pintype "bidirectional"))
      (node (ref "L7") (pin "1") (pinfunction "1_1") (pintype "bidirectional"))
    )
    (net (code "23") (name "LX2") (class "Default")
      (node (ref "IC9") (pin "D2") (pinfunction "SW2_1_D2") (pintype "bidirectional"))
      (node (ref "IC9") (pin "D3") (pinfunction "SW2_2_D3") (pintype "bidirectional"))
      (node (ref "L7") (pin "2") (pinfunction "2_2") (pintype "bidirectional"))
    )
    (net (code "24") (name "MOSI") (class "Default")
      (node (ref "J1") (pin "14") (pinfunction "14_14") (pintype "bidirectional"))
      (node (ref "U1") (pin "P$B13") (pinfunction "P0.03/AIN1_P$B13") (pintype "bidirectional"))
    )
    (net (code "25") (name "Net-(ANT1-FEED)") (class "Default")
      (node (ref "ANT1") (pin "1") (pinfunction "FEED_1") (pintype "input"))
      (node (ref "C22") (pin "1") (pinfunction "1_1") (pintype "passive"))
      (node (ref "C4") (pin "1") (pinfunction "1_1") (pintype "passive"))
      (node (ref "L1") (pin "2") (pinfunction "2_2") (pintype "passive"))
    )
    (net (code "26") (name "Net-(D2-K)") (class "Default")
      (node (ref "C2-EP-DR") (pin "1") (pinfunction "1_1") (pintype "passive"))
      (node (ref "D2") (pin "1") (pinfunction "K_1") (pintype "bidirectional"))
      (node (ref "D4") (pin "2") (pinfunction "A_2") (pintype "bidirectional"))
    )
    (net (code "27") (name "Net-(D5-A)") (class "Default")
      (node (ref "C2-EP-DR") (pin "2") (pinfunction "2_2") (pintype "passive"))
      (node (ref "D5") (pin "2") (pinfunction "A_2") (pintype "bidirectional"))
      (node (ref "L5") (pin "1") (pinfunction "1_1") (pintype "passive"))
      (node (ref "Q3") (pin "3") (pinfunction "D_3") (pintype "bidirectional"))
    )
    (net (code "28") (name "Net-(EPD_C1-Pad2)") (class "Default")
      (node (ref "EPD_C1") (pin "2") (pinfunction "2_2") (pintype "passive"))
      (node (ref "J1") (pin "5") (pinfunction "5_5") (pintype "bidirectional"))
    )
    (net (code "29") (name "Net-(EPD_C2-Pad2)") (class "Default")
      (node (ref "EPD_C2") (pin "2") (pinfunction "2_2") (pintype "passive"))
      (node (ref "J1") (pin "4") (pinfunction "4_4") (pintype "bidirectional"))
    )
    (net (code "30") (name "Net-(EPD_C6-Pad2)") (class "Default")
      (node (ref "EPD_C6") (pin "2") (pinfunction "2_2") (pintype "passive"))
      (node (ref "J1") (pin "18") (pinfunction "18_18") (pintype "bidirectional"))
    )
    (net (code "31") (name "Net-(EPD_C7-Pad2)") (class "Default")
      (node (ref "EPD_C7") (pin "2") (pinfunction "2_2") (pintype "passive"))
      (node (ref "J1") (pin "19") (pinfunction "19_19") (pintype "bidirectional"))
    )
    (net (code "32") (name "Net-(EPD_C8-Pad2)") (class "Default")
      (node (ref "EPD_C8") (pin "2") (pinfunction "2_2") (pintype "passive"))
      (node (ref "J1") (pin "20") (pinfunction "20_20") (pintype "bidirectional"))
    )
    (net (code "33") (name "Net-(EPD_C10-Pad2)") (class "Default")
      (node (ref "EPD_C10") (pin "2") (pinfunction "2_2") (pintype "passive"))
      (node (ref "J1") (pin "22") (pinfunction "22_22") (pintype "bidirectional"))
    )
    (net (code "34") (name "Net-(EPD_C12-Pad2)") (class "Default")
      (node (ref "EPD_C12") (pin "2") (pinfunction "2_2") (pintype "passive"))
      (node (ref "J1") (pin "24") (pinfunction "24_24") (pintype "bidirectional"))
    )
    (net (code "35") (name "Net-(IC1-TS{slash}MR)") (class "Default")
      (node (ref "IC1") (pin "D1") (pinfunction "TS/MR_D1") (pintype "bidirectional"))
      (node (ref "R9") (pin "2") (pinfunction "2_2") (pintype "bidirectional"))
    )
    (net (code "36") (name "Net-(IC2-REG)") (class "Default")
      (node (ref "C32") (pin "2") (pinfunction "2_2") (pintype "passive"))
      (node (ref "IC2") (pin "A2") (pinfunction "REG_A2") (pintype "bidirectional"))
    )
    (net (code "37") (name "Net-(IC3-SDO)") (class "Default")
      (node (ref "IC3") (pin "1") (pinfunction "SDO_1") (pintype "bidirectional"))
      (node (ref "R3") (pin "1") (pinfunction "1_1") (pintype "bidirectional"))
    )
    (net (code "38") (name "Net-(IC9-SCL)") (class "Default")
      (node (ref "IC9") (pin "D1") (pinfunction "SCL_D1") (pintype "bidirectional"))
      (node (ref "R4") (pin "1") (pinfunction "1_1") (pintype "bidirectional"))
    )
    (net (code "39") (name "Net-(IC9-SDA)") (class "Default")
      (node (ref "IC9") (pin "E1") (pinfunction "SDA_E1") (pintype "bidirectional"))
      (node (ref "R2") (pin "1") (pinfunction "1_1") (pintype "bidirectional"))
    )
    (net (code "40") (name "Net-(J4-CC1)") (class "Default")
      (node (ref "J4") (pin "A5") (pinfunction "CC1_A5") (pintype "bidirectional"))
      (node (ref "R1_USB") (pin "2") (pinfunction "2_2") (pintype "bidirectional"))
    )
    (net (code "41") (name "Net-(J4-CC2)") (class "Default")
      (node (ref "J4") (pin "B5") (pinfunction "CC2_B5") (pintype "bidirectional"))
      (node (ref "R2_USB") (pin "1") (pinfunction "1_1") (pintype "bidirectional"))
    )
    (net (code "42") (name "Net-(L2-Pad2)") (class "Default")
      (node (ref "L2") (pin "2") (pinfunction "2_2") (pintype "passive"))
      (node (ref "L3") (pin "1") (pinfunction "1_1") (pintype "passive"))
    )
    (net (code "43") (name "Net-(R1_EP_DR-Pad1)") (class "Default")
      (node (ref "R1_EP_DR") (pin "1") (pinfunction "1_1") (pintype "bidirectional"))
      (node (ref "R_TYPE_SEL") (pin "2") (pinfunction "2_2") (pintype "bidirectional"))
      (node (ref "SJ1") (pin "2") (pinfunction "2_2") (pintype "passive"))
    )
    (net (code "44") (name "Net-(U1-ANT)") (class "Default")
      (node (ref "C3") (pin "1") (pinfunction "1_1") (pintype "passive"))
      (node (ref "L1") (pin "1") (pinfunction "1_1") (pintype "passive"))
      (node (ref "U1") (pin "P$H23") (pinfunction "ANT_P$H23") (pintype "bidirectional"))
    )
    (net (code "45") (name "Net-(U1-DCC)") (class "Default")
      (node (ref "L2") (pin "1") (pinfunction "1_1") (pintype "passive"))
      (node (ref "U1") (pin "P$B3") (pinfunction "DCC_P$B3") (pintype "output"))
    )
    (net (code "46") (name "Net-(U1-DEC2)") (class "Default")
      (node (ref "C13") (pin "1") (pinfunction "1_1") (pintype "passive"))
      (node (ref "U1") (pin "P$A18") (pinfunction "DEC2_P$A18") (pintype "bidirectional"))
    )
    (net (code "47") (name "Net-(U1-DEC3V3)") (class "Default")
      (node (ref "C20") (pin "1") (pinfunction "1_1") (pintype "passive"))
      (node (ref "U1") (pin "P$AC5") (pinfunction "DEC3V3_P$AC5") (pintype "bidirectional"))
    )
    (net (code "48") (name "Net-(U1-DEC5)") (class "Default")
      (node (ref "C9") (pin "1") (pinfunction "1_1") (pintype "passive"))
      (node (ref "U1") (pin "P$N24") (pinfunction "DEC5_P$N24") (pintype "bidirectional"))
    )
    (net (code "49") (name "Net-(U1-XC1)") (class "Default")
      (node (ref "C1") (pin "1") (pinfunction "1_1") (pintype "passive"))
      (node (ref "U1") (pin "P$B24") (pinfunction "XC1_P$B24") (pintype "input"))
      (node (ref "X1") (pin "1") (pinfunction "1_1") (pintype "passive"))
    )
    (net (code "50") (name "Net-(U1-XC2)") (class "Default")
      (node (ref "C2") (pin "1") (pinfunction "1_1") (pintype "passive"))
      (node (ref "U1") (pin "P$A23") (pinfunction "XC2_P$A23") (pintype "output"))
      (node (ref "X1") (pin "3") (pinfunction "3_3") (pintype "passive"))
    )
    (net (code "51") (name "OUT+") (class "Default")
      (node (ref "IC2") (pin "A3") (pinfunction "OUT+_A3") (pintype "bidirectional"))
      (node (ref "OP") (pin "TP") (pinfunction "TP_TP") (pintype "input"))
    )
    (net (code "52") (name "OUT-") (class "Default")
      (node (ref "IC2") (pin "C3") (pinfunction "OUT-_C3") (pintype "bidirectional"))
      (node (ref "ON") (pin "TP") (pinfunction "TP_TP") (pintype "input"))
    )
    (net (code "53") (name "P0.04") (class "Default")
      (node (ref "U1") (pin "P$J1") (pinfunction "P0.04/AIN2_P$J1") (pintype "bidirectional"))
    )
    (net (code "54") (name "P0.09") (class "Default")
      (node (ref "U1") (pin "P$L24") (pinfunction "P0.09/NFC1_P$L24") (pintype "bidirectional"))
    )
    (net (code "55") (name "P0.13") (class "Default")
      (node (ref "C30") (pin "2") (pinfunction "2_2") (pintype "passive"))
      (node (ref "R5") (pin "1") (pinfunction "1_1") (pintype "bidirectional"))
      (node (ref "SW_UP") (pin "2") (pinfunction "2_2") (pintype "passive"))
      (node (ref "U1") (pin "P$AD8") (pinfunction "P0.13_P$AD8") (pintype "bidirectional"))
    )
    (net (code "56") (name "P0.14") (class "Default")
      (node (ref "C31") (pin "2") (pinfunction "2_2") (pintype "passive"))
      (node (ref "R8") (pin "1") (pinfunction "1_1") (pintype "bidirectional"))
      (node (ref "SW_ENT") (pin "2") (pinfunction "2_2") (pintype "passive"))
      (node (ref "U1") (pin "P$AC9") (pinfunction "P0.14_P$AC9") (pintype "bidirectional"))
    )
    (net (code "57") (name "P0.19") (class "Default")
      (node (ref "U1") (pin "P$AC15") (pinfunction "P0.19_P$AC15") (pintype "bidirectional"))
    )
    (net (code "58") (name "P0.20") (class "Default")
      (node (ref "U1") (pin "P$AD16") (pinfunction "P0.20_P$AD16") (pintype "bidirectional"))
    )
    (net (code "59") (name "P0.21") (class "Default")
      (node (ref "U1") (pin "P$AC17") (pinfunction "P0.21_P$AC17") (pintype "bidirectional"))
    )
    (net (code "60") (name "P0.22") (class "Default")
      (node (ref "U1") (pin "P$AD18") (pinfunction "P0.22_P$AD18") (pintype "bidirectional"))
    )
    (net (code "61") (name "P0.23") (class "Default")
      (node (ref "U1") (pin "P$AC19") (pinfunction "P0.23_P$AC19") (pintype "bidirectional"))
    )
    (net (code "62") (name "P0.24") (class "Default")
      (node (ref "U1") (pin "P$AD20") (pinfunction "P0.24_P$AD20") (pintype "bidirectional"))
    )
    (net (code "63") (name "P0.25") (class "Default")
      (node (ref "U1") (pin "P$AC21") (pinfunction "P0.25_P$AC21") (pintype "bidirectional"))
    )
    (net (code "64") (name "P0.26") (class "Default")
      (node (ref "U1") (pin "P$G1") (pinfunction "P0.26_P$G1") (pintype "bidirectional"))
    )
    (net (code "65") (name "P0.27") (class "Default")
      (node (ref "U1") (pin "P$H2") (pinfunction "P0.27_P$H2") (pintype "bidirectional"))
    )
    (net (code "66") (name "P0.28") (class "Default")
      (node (ref "U1") (pin "P$B11") (pinfunction "P0.28/AIN4_P$B11") (pintype "bidirectional"))
    )
    (net (code "67") (name "P0.29") (class "Default")
      (node (ref "U1") (pin "P$A10") (pinfunction "P0.29/AIN5_P$A10") (pintype "bidirectional"))
    )
    (net (code "68") (name "P0.30") (class "Default")
      (node (ref "U1") (pin "P$B9") (pinfunction "P0.30/AIN6_P$B9") (pintype "bidirectional"))
    )
    (net (code "69") (name "P0.31") (class "Default")
      (node (ref "U1") (pin "P$A8") (pinfunction "P0.31/AIN7_P$A8") (pintype "bidirectional"))
    )
    (net (code "70") (name "P1.01") (class "Default")
      (node (ref "Q1") (pin "1") (pinfunction "G_1") (pintype "bidirectional"))
      (node (ref "R_PWR_EPD") (pin "1") (pinfunction "1_1") (pintype "bidirectional"))
      (node (ref "U1") (pin "P$Y23") (pinfunction "P1.01_P$Y23") (pintype "bidirectional"))
    )
    (net (code "71") (name "P1.02") (class "Default")
      (node (ref "C29") (pin "2") (pinfunction "2_2") (pintype "passive"))
      (node (ref "R7") (pin "1") (pinfunction "1_1") (pintype "bidirectional"))
      (node (ref "SW_DN") (pin "2") (pinfunction "2_2") (pintype "passive"))
      (node (ref "U1") (pin "P$W24") (pinfunction "P1.02_P$W24") (pintype "bidirectional"))
    )
    (net (code "72") (name "P1.03") (class "Default")
      (node (ref "U1") (pin "P$V23") (pinfunction "P1.03_P$V23") (pintype "bidirectional"))
    )
    (net (code "73") (name "P1.04") (class "Default")
      (node (ref "U1") (pin "P$U24") (pinfunction "P1.04_P$U24") (pintype "bidirectional"))
    )
    (net (code "74") (name "P1.05") (class "Default")
      (node (ref "U1") (pin "P$T23") (pinfunction "P1.05_P$T23") (pintype "bidirectional"))
    )
    (net (code "75") (name "P1.06") (class "Default")
      (node (ref "U1") (pin "P$R24") (pinfunction "P1.06_P$R24") (pintype "bidirectional"))
    )
    (net (code "76") (name "P1.07") (class "Default")
      (node (ref "U1") (pin "P$P23") (pinfunction "P1.07_P$P23") (pintype "bidirectional"))
    )
    (net (code "77") (name "P1.09") (class "Default")
      (node (ref "U1") (pin "P$R1") (pinfunction "P1.09_P$R1") (pintype "bidirectional"))
    )
    (net (code "78") (name "P1.10") (class "Default")
      (node (ref "U1") (pin "P$A20") (pinfunction "P1.10_P$A20") (pintype "bidirectional"))
    )
    (net (code "79") (name "P1.11") (class "Default")
      (node (ref "U1") (pin "P$B19") (pinfunction "P1.11_P$B19") (pintype "bidirectional"))
    )
    (net (code "80") (name "P1.12") (class "Default")
      (node (ref "U1") (pin "P$B17") (pinfunction "P1.12_P$B17") (pintype "bidirectional"))
    )
    (net (code "81") (name "P1.13") (class "Default")
      (node (ref "U1") (pin "P$A16") (pinfunction "P1.13_P$A16") (pintype "bidirectional"))
    )
    (net (code "82") (name "P1.14") (class "Default")
      (node (ref "U1") (pin "P$B15") (pinfunction "P1.14_P$B15") (pintype "bidirectional"))
    )
    (net (code "83") (name "P1.15") (class "Default")
      (node (ref "U1") (pin "P$A14") (pinfunction "P1.15_P$A14") (pintype "bidirectional"))
    )
    (net (code "84") (name "PMIC_INT") (class "Default")
      (node (ref "IC1") (pin "A1") (pinfunction "~{INT}_A1") (pintype "bidirectional"))
      (node (ref "U1") (pin "P$T2") (pinfunction "P0.11_P$T2") (pintype "bidirectional"))
    )
    (net (code "85") (name "PREVGH") (class "Default")
      (node (ref "D5") (pin "1") (pinfunction "K_1") (pintype "bidirectional"))
      (node (ref "EPD_C9") (pin "2") (pinfunction "2_2") (pintype "passive"))
      (node (ref "J1") (pin "21") (pinfunction "21_21") (pintype "bidirectional"))
    )
    (net (code "86") (name "PREVGL") (class "Default")
      (node (ref "D2") (pin "2") (pinfunction "A_2") (pintype "bidirectional"))
      (node (ref "EPD_C11") (pin "2") (pinfunction "2_2") (pintype "passive"))
      (node (ref "J1") (pin "23") (pinfunction "23_23") (pintype "bidirectional"))
    )
    (net (code "87") (name "RESE") (class "Default")
      (node (ref "J1") (pin "3") (pinfunction "3_3") (pintype "bidirectional"))
      (node (ref "Q3") (pin "2") (pinfunction "S_2") (pintype "bidirectional"))
      (node (ref "R1_EP_DR") (pin "2") (pinfunction "2_2") (pintype "bidirectional"))
    )
    (net (code "88") (name "RESET") (class "Default")
      (node (ref "J2") (pin "6") (pinfunction "6_6") (pintype "bidirectional"))
      (node (ref "RESET") (pin "TP") (pinfunction "TP_TP") (pintype "input"))
      (node (ref "U1") (pin "P$AC13") (pinfunction "P0.18/RESET_P$AC13") (pintype "bidirectional"))
    )
    (net (code "89") (name "SCK") (class "Default")
      (node (ref "J1") (pin "13") (pinfunction "13_13") (pintype "bidirectional"))
      (node (ref "U1") (pin "P$A12") (pinfunction "P0.02/AIN0_P$A12") (pintype "bidirectional"))
    )
    (net (code "90") (name "SCL") (class "Default")
      (node (ref "IC1") (pin "B1") (pinfunction "SCL_B1") (pintype "bidirectional"))
      (node (ref "IC2") (pin "C1") (pinfunction "SCL_C1") (pintype "bidirectional"))
      (node (ref "IC3") (pin "12") (pinfunction "SCX_12") (pintype "bidirectional"))
      (node (ref "R17") (pin "2") (pinfunction "2_2") (pintype "bidirectional"))
      (node (ref "R4") (pin "2") (pinfunction "2_2") (pintype "bidirectional"))
      (node (ref "TP_SCL") (pin "TP") (pinfunction "TP_TP") (pintype "input"))
      (node (ref "U1") (pin "P$M2") (pinfunction "P0.07_P$M2") (pintype "bidirectional"))
      (node (ref "U3") (pin "7") (pinfunction "SCL_7") (pintype "input"))
    )
    (net (code "91") (name "SDA") (class "Default")
      (node (ref "IC1") (pin "C1") (pinfunction "SDA_C1") (pintype "bidirectional"))
      (node (ref "IC2") (pin "B2") (pinfunction "SDA_B2") (pintype "bidirectional"))
      (node (ref "IC3") (pin "2") (pinfunction "SDX_2") (pintype "bidirectional"))
      (node (ref "R18") (pin "2") (pinfunction "2_2") (pintype "bidirectional"))
      (node (ref "R2") (pin "2") (pinfunction "2_2") (pintype "bidirectional"))
      (node (ref "SDA") (pin "TP") (pinfunction "TP_TP") (pintype "input"))
      (node (ref "U1") (pin "P$L1") (pinfunction "P0.06_P$L1") (pintype "bidirectional"))
      (node (ref "U3") (pin "8") (pinfunction "SDA_8") (pintype "bidirectional"))
    )
    (net (code "92") (name "SWDCLK") (class "Default")
      (node (ref "J2") (pin "4") (pinfunction "4_4") (pintype "bidirectional"))
      (node (ref "SWDCLK") (pin "TP") (pinfunction "TP_TP") (pintype "input"))
      (node (ref "U1") (pin "P$AA24") (pinfunction "SWDCLK_P$AA24") (pintype "input"))
    )
    (net (code "93") (name "SWDIO") (class "Default")
      (node (ref "J2") (pin "2") (pinfunction "2_2") (pintype "bidirectional"))
      (node (ref "SWDIO") (pin "TP") (pinfunction "TP_TP") (pintype "input"))
      (node (ref "U1") (pin "P$AC24") (pinfunction "SWDIO_P$AC24") (pintype "bidirectional"))
    )
    (net (code "94") (name "SWO") (class "Default")
      (node (ref "SWO") (pin "TP") (pinfunction "TP_TP") (pintype "input"))
      (node (ref "U1") (pin "P$AD22") (pinfunction "P1.00_P$AD22") (pintype "bidirectional"))
    )
    (net (code "95") (name "VBAT") (class "Default")
      (node (ref "C27") (pin "2") (pinfunction "2_2") (pintype "passive"))
      (node (ref "C37") (pin "2") (pinfunction "2_2") (pintype "passive"))
      (node (ref "IC1") (pin "C2") (pinfunction "BAT_C2") (pintype "bidirectional"))
      (node (ref "U3") (pin "2") (pinfunction "CELL_2") (pintype "power_in"))
      (node (ref "U3") (pin "3") (pinfunction "VDD_3") (pintype "power_in"))
      (node (ref "VBAT") (pin "TP") (pinfunction "TP_TP") (pintype "input"))
    )
    (net (code "96") (name "VBUS") (class "Default")
      (node (ref "C21") (pin "1") (pinfunction "1_1") (pintype "passive"))
      (node (ref "C38") (pin "2") (pinfunction "2_2") (pintype "passive"))
      (node (ref "C42") (pin "2") (pinfunction "2_2") (pintype "passive"))
      (node (ref "C43") (pin "1") (pinfunction "1_1") (pintype "passive"))
      (node (ref "D3") (pin "5") (pinfunction "VBUS_5") (pintype "bidirectional"))
      (node (ref "IC1") (pin "A2") (pinfunction "IN_A2") (pintype "bidirectional"))
      (node (ref "J4") (pin "A4_B9") (pinfunction "VBUS_A4_B9") (pintype "power_in"))
      (node (ref "J4") (pin "A9_B4") (pinfunction "VBUS_A9_B4") (pintype "power_in"))
      (node (ref "U1") (pin "P$AD2") (pinfunction "VBUS_P$AD2") (pintype "power_in"))
    )
    (net (code "97") (name "VREG") (class "Default")
      (node (ref "C23") (pin "1") (pinfunction "1_1") (pintype "passive"))
      (node (ref "C24") (pin "2") (pinfunction "2_2") (pintype "passive"))
      (node (ref "C39") (pin "1") (pinfunction "1_1") (pintype "passive"))
      (node (ref "IC1") (pin "B2") (pinfunction "SYS_B2") (pintype "bidirectional"))
      (node (ref "IC9") (pin "A1") (pinfunction "EN_A1") (pintype "bidirectional"))
      (node (ref "IC9") (pin "A2") (pinfunction "VIN_1_A2") (pintype "bidirectional"))
      (node (ref "IC9") (pin "A3") (pinfunction "VIN_2_A3") (pintype "bidirectional"))
      (node (ref "VREG") (pin "TP") (pinfunction "TP_TP") (pintype "input"))
    )
    (net (code "98") (name "unconnected-(ANT1-NC-Pad2)") (class "Default")
      (node (ref "ANT1") (pin "2") (pinfunction "NC_2") (pintype "no_connect"))
    )
    (net (code "99") (name "unconnected-(IC3-ASCL-Pad11)") (class "Default")
      (node (ref "IC3") (pin "11") (pinfunction "ASCL_11") (pintype "bidirectional"))
    )
    (net (code "100") (name "unconnected-(IC3-ASDA-Pad4)") (class "Default")
      (node (ref "IC3") (pin "4") (pinfunction "ASDA_4") (pintype "bidirectional"))
    )
    (net (code "101") (name "unconnected-(J1-Pad1)") (class "Default")
      (node (ref "J1") (pin "1") (pinfunction "1_1") (pintype "bidirectional"))
    )
    (net (code "102") (name "unconnected-(J1-Pad6)") (class "Default")
      (node (ref "J1") (pin "6") (pinfunction "6_6") (pintype "bidirectional"))
    )
    (net (code "103") (name "unconnected-(J1-Pad7)") (class "Default")
      (node (ref "J1") (pin "7") (pinfunction "7_7") (pintype "bidirectional"))
    )
    (net (code "104") (name "unconnected-(J4-SBU1-PadA8)") (class "Default")
      (node (ref "J4") (pin "A8") (pinfunction "SBU1_A8") (pintype "bidirectional"))
    )
    (net (code "105") (name "unconnected-(J4-SBU2-PadB8)") (class "Default")
      (node (ref "J4") (pin "B8") (pinfunction "SBU2_B8") (pintype "bidirectional"))
    )
    (net (code "106") (name "unconnected-(U1-DCCH-PadP$AB2)") (class "Default")
      (node (ref "U1") (pin "P$AB2") (pinfunction "DCCH_P$AB2") (pintype "bidirectional"))
    )
  )
)
